# schema_v3_2.net
KiCad netlist of a schematic drawn in EAGLE
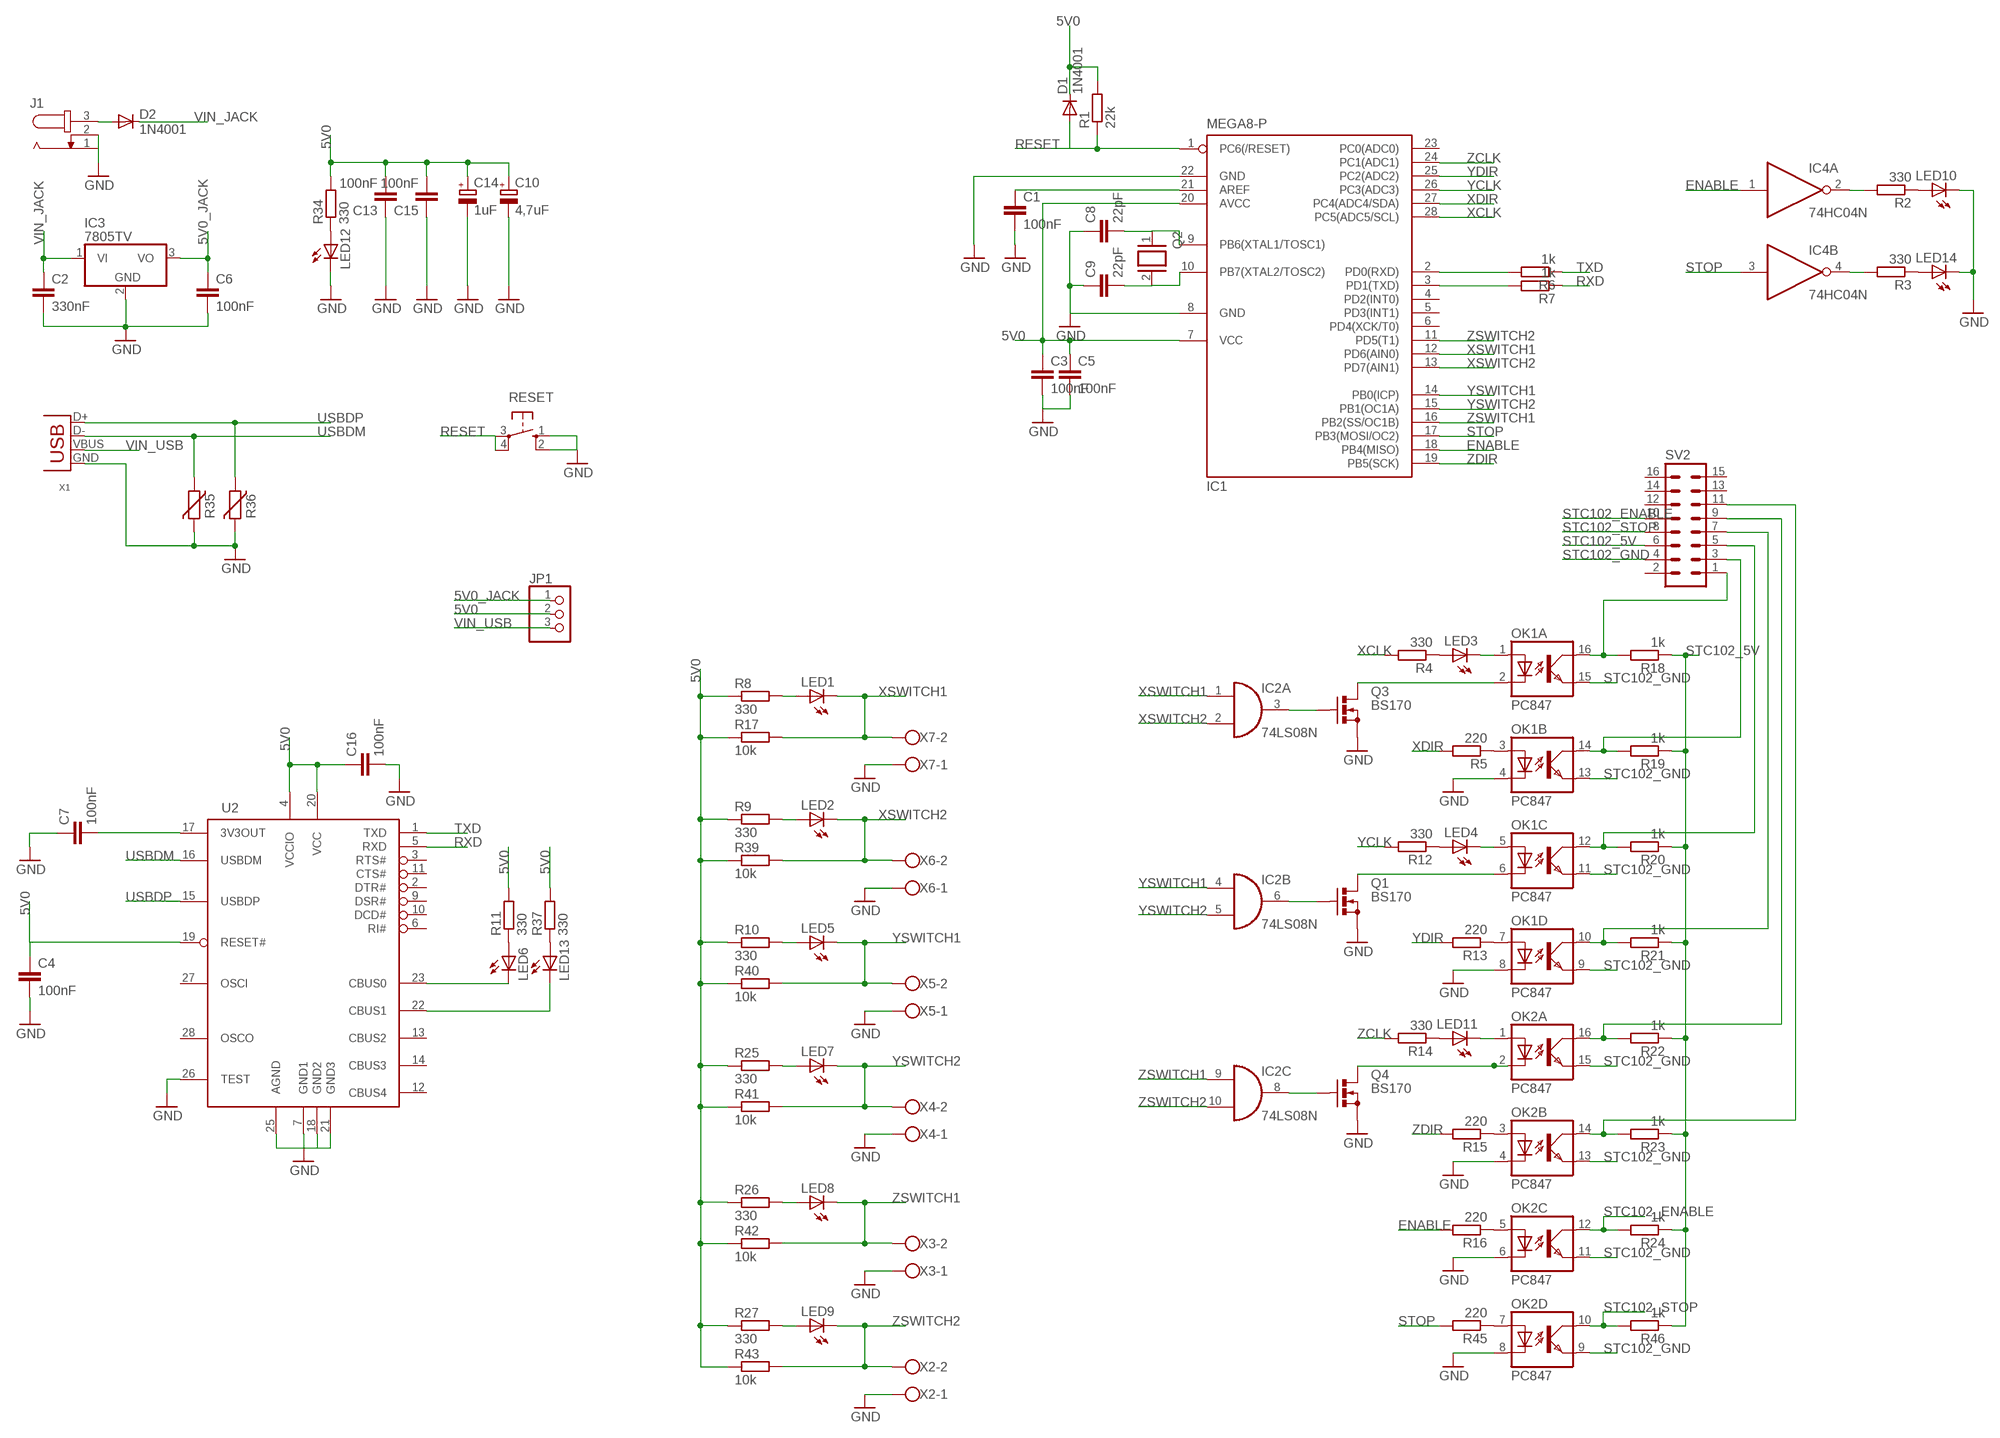
[diagram p0: schematic, sheet 1]

(export (version "E")
  (design (tool "Eeschema 10.0.6"))
  (components
    (comp (ref "C1")
      (value "100nF")
      (footprint "eagle-import:C0805")
      (libsource (lib "eagle-import") (part "C-EUC0805"))
    )
    (comp (ref "C2")
      (value "330nF")
      (footprint "eagle-import:C025-025X050")
      (libsource (lib "eagle-import") (part "C-EU025-025X050"))
    )
    (comp (ref "C3")
      (value "100nF")
      (footprint "eagle-import:C025-025X050")
      (libsource (lib "eagle-import") (part "C-EU025-025X050"))
    )
    (comp (ref "C4")
      (value "100nF")
      (footprint "eagle-import:C0603K")
      (libsource (lib "eagle-import") (part "C-EUC0603K"))
    )
    (comp (ref "C5")
      (value "100nF")
      (footprint "eagle-import:C025-025X050")
      (libsource (lib "eagle-import") (part "C-EU025-025X050"))
    )
    (comp (ref "C6")
      (value "100nF")
      (footprint "eagle-import:C025-025X050")
      (libsource (lib "eagle-import") (part "C-EU025-025X050"))
    )
    (comp (ref "C7")
      (value "100nF")
      (footprint "eagle-import:C0603K")
      (libsource (lib "eagle-import") (part "C-EUC0603K"))
    )
    (comp (ref "C8")
      (value "22pF")
      (footprint "eagle-import:C025-025X050")
      (libsource (lib "eagle-import") (part "C-EU025-025X050"))
    )
    (comp (ref "C9")
      (value "22pF")
      (footprint "eagle-import:C025-025X050")
      (libsource (lib "eagle-import") (part "C-EU025-025X050"))
    )
    (comp (ref "C10")
      (value "4,7uF")
      (footprint "eagle-import:E2,5-5")
      (libsource (lib "eagle-import") (part "CPOL-EUE2.5-5"))
    )
    (comp (ref "C13")
      (value "100nF")
      (footprint "eagle-import:C025-025X050")
      (libsource (lib "eagle-import") (part "C-EU025-025X050"))
    )
    (comp (ref "C14")
      (value "1uF")
      (footprint "eagle-import:E2,5-5")
      (libsource (lib "eagle-import") (part "CPOL-EUE2.5-5"))
    )
    (comp (ref "C15")
      (value "100nF")
      (footprint "eagle-import:C025-025X050")
      (libsource (lib "eagle-import") (part "C-EU025-025X050"))
    )
    (comp (ref "C16")
      (value "100nF")
      (footprint "eagle-import:C0603K")
      (libsource (lib "eagle-import") (part "C-EUC0603K"))
    )
    (comp (ref "D1")
      (value "1N4001")
      (footprint "eagle-import:DO41-10")
      (libsource (lib "eagle-import") (part "1N4004"))
    )
    (comp (ref "D2")
      (value "1N4001")
      (footprint "eagle-import:DO41-10")
      (libsource (lib "eagle-import") (part "1N4004"))
    )
    (comp (ref "IC1")
      (value "MEGA8-P")
      (footprint "eagle-import:DIL28-3")
      (libsource (lib "eagle-import") (part "MEGA8-P"))
    )
    (comp (ref "IC2")
      (value "74LS08N")
      (footprint "eagle-import:DIL14")
      (libsource (lib "eagle-import") (part "7408NLS"))
    )
    (comp (ref "IC3")
      (value "7805TV")
      (footprint "eagle-import:TO220V")
      (libsource (lib "eagle-import") (part "78TV05"))
    )
    (comp (ref "IC4")
      (value "74HC04N")
      (footprint "eagle-import:DIL14")
      (libsource (lib "eagle-import") (part "7404NHC"))
    )
    (comp (ref "J1")
      (value "JACK-PLUG0")
      (footprint "eagle-import:SPC4077")
      (libsource (lib "eagle-import") (part "JACK-PLUG0"))
    )
    (comp (ref "JP1")
      (value "PINHD-1X3")
      (footprint "eagle-import:1X03")
      (libsource (lib "eagle-import") (part "PINHD-1X3"))
    )
    (comp (ref "LED1")
      (value "LED3MM")
      (footprint "eagle-import:LED3MM")
      (libsource (lib "eagle-import") (part "LED3MM"))
    )
    (comp (ref "LED2")
      (value "LED3MM")
      (footprint "eagle-import:LED3MM")
      (libsource (lib "eagle-import") (part "LED3MM"))
    )
    (comp (ref "LED3")
      (value "LED3MM")
      (footprint "eagle-import:LED3MM")
      (libsource (lib "eagle-import") (part "LED3MM"))
    )
    (comp (ref "LED4")
      (value "LED3MM")
      (footprint "eagle-import:LED3MM")
      (libsource (lib "eagle-import") (part "LED3MM"))
    )
    (comp (ref "LED5")
      (value "LED3MM")
      (footprint "eagle-import:LED3MM")
      (libsource (lib "eagle-import") (part "LED3MM"))
    )
    (comp (ref "LED6")
      (value "LED3MM")
      (footprint "eagle-import:LED3MM")
      (libsource (lib "eagle-import") (part "LED3MM"))
    )
    (comp (ref "LED7")
      (value "LED3MM")
      (footprint "eagle-import:LED3MM")
      (libsource (lib "eagle-import") (part "LED3MM"))
    )
    (comp (ref "LED8")
      (value "LED3MM")
      (footprint "eagle-import:LED3MM")
      (libsource (lib "eagle-import") (part "LED3MM"))
    )
    (comp (ref "LED9")
      (value "LED3MM")
      (footprint "eagle-import:LED3MM")
      (libsource (lib "eagle-import") (part "LED3MM"))
    )
    (comp (ref "LED10")
      (value "LED3MM")
      (footprint "eagle-import:LED3MM")
      (libsource (lib "eagle-import") (part "LED3MM"))
    )
    (comp (ref "LED11")
      (value "LED3MM")
      (footprint "eagle-import:LED3MM")
      (libsource (lib "eagle-import") (part "LED3MM"))
    )
    (comp (ref "LED12")
      (value "LED3MM")
      (footprint "eagle-import:LED3MM")
      (libsource (lib "eagle-import") (part "LED3MM"))
    )
    (comp (ref "LED13")
      (value "LED3MM")
      (footprint "eagle-import:LED3MM")
      (libsource (lib "eagle-import") (part "LED3MM"))
    )
    (comp (ref "LED14")
      (value "LED3MM")
      (footprint "eagle-import:LED3MM")
      (libsource (lib "eagle-import") (part "LED3MM"))
    )
    (comp (ref "OK1")
      (value "PC847")
      (footprint "eagle-import:DIL16")
      (libsource (lib "eagle-import") (part "PC847"))
    )
    (comp (ref "OK2")
      (value "PC847")
      (footprint "eagle-import:DIL16")
      (libsource (lib "eagle-import") (part "PC847"))
    )
    (comp (ref "Q1")
      (value "BS170")
      (footprint "eagle-import:SOT54E")
      (libsource (lib "eagle-import") (part "BS170"))
    )
    (comp (ref "Q2")
      (value "XTAL/S")
      (footprint "eagle-import:QS")
      (libsource (lib "eagle-import") (part "XTAL/S"))
    )
    (comp (ref "Q3")
      (value "BS170")
      (footprint "eagle-import:SOT54E")
      (libsource (lib "eagle-import") (part "BS170"))
    )
    (comp (ref "Q4")
      (value "BS170")
      (footprint "eagle-import:SOT54E")
      (libsource (lib "eagle-import") (part "BS170"))
    )
    (comp (ref "R1")
      (value "22k")
      (footprint "eagle-import:0207_10")
      (libsource (lib "eagle-import") (part "R-EU_0207/10"))
    )
    (comp (ref "R2")
      (value "330")
      (footprint "eagle-import:0207_10")
      (libsource (lib "eagle-import") (part "R-EU_0207/10"))
    )
    (comp (ref "R3")
      (value "330")
      (footprint "eagle-import:0207_10")
      (libsource (lib "eagle-import") (part "R-EU_0207/10"))
    )
    (comp (ref "R4")
      (value "330")
      (footprint "eagle-import:0207_10")
      (libsource (lib "eagle-import") (part "R-EU_0207/10"))
    )
    (comp (ref "R5")
      (value "220")
      (footprint "eagle-import:0207_10")
      (libsource (lib "eagle-import") (part "R-EU_0207/10"))
    )
    (comp (ref "R6")
      (value "1k")
      (footprint "eagle-import:0207_10")
      (libsource (lib "eagle-import") (part "R-EU_0207/10"))
    )
    (comp (ref "R7")
      (value "1k")
      (footprint "eagle-import:0207_10")
      (libsource (lib "eagle-import") (part "R-EU_0207/10"))
    )
    (comp (ref "R8")
      (value "330")
      (footprint "eagle-import:0207_10")
      (libsource (lib "eagle-import") (part "R-EU_0207/10"))
    )
    (comp (ref "R9")
      (value "330")
      (footprint "eagle-import:0207_10")
      (libsource (lib "eagle-import") (part "R-EU_0207/10"))
    )
    (comp (ref "R10")
      (value "330")
      (footprint "eagle-import:0207_10")
      (libsource (lib "eagle-import") (part "R-EU_0207/10"))
    )
    (comp (ref "R11")
      (value "330")
      (footprint "eagle-import:0207_10")
      (libsource (lib "eagle-import") (part "R-EU_0207/10"))
    )
    (comp (ref "R12")
      (value "330")
      (footprint "eagle-import:0207_10")
      (libsource (lib "eagle-import") (part "R-EU_0207/10"))
    )
    (comp (ref "R13")
      (value "220")
      (footprint "eagle-import:0207_10")
      (libsource (lib "eagle-import") (part "R-EU_0207/10"))
    )
    (comp (ref "R14")
      (value "330")
      (footprint "eagle-import:0207_10")
      (libsource (lib "eagle-import") (part "R-EU_0207/10"))
    )
    (comp (ref "R15")
      (value "220")
      (footprint "eagle-import:0207_10")
      (libsource (lib "eagle-import") (part "R-EU_0207/10"))
    )
    (comp (ref "R16")
      (value "220")
      (footprint "eagle-import:0207_10")
      (libsource (lib "eagle-import") (part "R-EU_0207/10"))
    )
    (comp (ref "R17")
      (value "10k")
      (footprint "eagle-import:0207_10")
      (libsource (lib "eagle-import") (part "R-EU_0207/10"))
    )
    (comp (ref "R18")
      (value "1k")
      (footprint "eagle-import:0207_10")
      (libsource (lib "eagle-import") (part "R-EU_0207/10"))
    )
    (comp (ref "R19")
      (value "1k")
      (footprint "eagle-import:0207_10")
      (libsource (lib "eagle-import") (part "R-EU_0207/10"))
    )
    (comp (ref "R20")
      (value "1k")
      (footprint "eagle-import:0207_10")
      (libsource (lib "eagle-import") (part "R-EU_0207/10"))
    )
    (comp (ref "R21")
      (value "1k")
      (footprint "eagle-import:0207_10")
      (libsource (lib "eagle-import") (part "R-EU_0207/10"))
    )
    (comp (ref "R22")
      (value "1k")
      (footprint "eagle-import:0207_10")
      (libsource (lib "eagle-import") (part "R-EU_0207/10"))
    )
    (comp (ref "R23")
      (value "1k")
      (footprint "eagle-import:0207_10")
      (libsource (lib "eagle-import") (part "R-EU_0207/10"))
    )
    (comp (ref "R24")
      (value "1k")
      (footprint "eagle-import:0207_10")
      (libsource (lib "eagle-import") (part "R-EU_0207/10"))
    )
    (comp (ref "R25")
      (value "330")
      (footprint "eagle-import:0207_10")
      (libsource (lib "eagle-import") (part "R-EU_0207/10"))
    )
    (comp (ref "R26")
      (value "330")
      (footprint "eagle-import:0207_10")
      (libsource (lib "eagle-import") (part "R-EU_0207/10"))
    )
    (comp (ref "R27")
      (value "330")
      (footprint "eagle-import:0207_10")
      (libsource (lib "eagle-import") (part "R-EU_0207/10"))
    )
    (comp (ref "R34")
      (value "330")
      (footprint "eagle-import:0207_10")
      (libsource (lib "eagle-import") (part "R-EU_0207/10"))
    )
    (comp (ref "R35")
      (value "VARISTORCN0603")
      (footprint "eagle-import:CT_CN0603")
      (libsource (lib "eagle-import") (part "VARISTORCN0603"))
    )
    (comp (ref "R36")
      (value "VARISTORCN0603")
      (footprint "eagle-import:CT_CN0603")
      (libsource (lib "eagle-import") (part "VARISTORCN0603"))
    )
    (comp (ref "R37")
      (value "330")
      (footprint "eagle-import:0207_10")
      (libsource (lib "eagle-import") (part "R-EU_0207/10"))
    )
    (comp (ref "R39")
      (value "10k")
      (footprint "eagle-import:0207_10")
      (libsource (lib "eagle-import") (part "R-EU_0207/10"))
    )
    (comp (ref "R40")
      (value "10k")
      (footprint "eagle-import:0207_10")
      (libsource (lib "eagle-import") (part "R-EU_0207/10"))
    )
    (comp (ref "R41")
      (value "10k")
      (footprint "eagle-import:0207_10")
      (libsource (lib "eagle-import") (part "R-EU_0207/10"))
    )
    (comp (ref "R42")
      (value "10k")
      (footprint "eagle-import:0207_10")
      (libsource (lib "eagle-import") (part "R-EU_0207/10"))
    )
    (comp (ref "R43")
      (value "10k")
      (footprint "eagle-import:0207_10")
      (libsource (lib "eagle-import") (part "R-EU_0207/10"))
    )
    (comp (ref "R45")
      (value "220")
      (footprint "eagle-import:0207_10")
      (libsource (lib "eagle-import") (part "R-EU_0207/10"))
    )
    (comp (ref "R46")
      (value "1k")
      (footprint "eagle-import:0207_10")
      (libsource (lib "eagle-import") (part "R-EU_0207/10"))
    )
    (comp (ref "RESET")
      (value "10-XX")
      (footprint "eagle-import:B3F-10XX")
      (fields (field (name "MPN") "B3F-1000"))
      (libsource (lib "eagle-import") (part "10-XX"))
    )
    (comp (ref "SV2")
      (value "MA08-2")
      (footprint "eagle-import:MA08-2")
      (libsource (lib "eagle-import") (part "MA08-2"))
    )
    (comp (ref "U2")
      (value "FT232RL")
      (footprint "eagle-import:SSOP28DB")
      (libsource (lib "eagle-import") (part "FT232RL"))
    )
    (comp (ref "X1")
      (value "USB-B-H")
      (footprint "eagle-import:USB-B-H")
      (libsource (lib "eagle-import") (part "USB-B-H"))
    )
    (comp (ref "X2")
      (value "W237-102")
      (footprint "eagle-import:W237-102")
      (fields (field (name "MPN") "237-102"))
      (libsource (lib "eagle-import") (part "W237-102"))
    )
    (comp (ref "X3")
      (value "W237-102")
      (footprint "eagle-import:W237-102")
      (fields (field (name "MPN") "237-102"))
      (libsource (lib "eagle-import") (part "W237-102"))
    )
    (comp (ref "X4")
      (value "W237-102")
      (footprint "eagle-import:W237-102")
      (fields (field (name "MPN") "237-102"))
      (libsource (lib "eagle-import") (part "W237-102"))
    )
    (comp (ref "X5")
      (value "W237-102")
      (footprint "eagle-import:W237-102")
      (fields (field (name "MPN") "237-102"))
      (libsource (lib "eagle-import") (part "W237-102"))
    )
    (comp (ref "X6")
      (value "W237-102")
      (footprint "eagle-import:W237-102")
      (fields (field (name "MPN") "237-102"))
      (libsource (lib "eagle-import") (part "W237-102"))
    )
    (comp (ref "X7")
      (value "W237-102")
      (footprint "eagle-import:W237-102")
      (fields (field (name "MPN") "237-102"))
      (libsource (lib "eagle-import") (part "W237-102"))
    )
  )
  (nets
    (net (code "1") (name "/5V0") (class "Default")
      (node (ref "C10") (pin "+") (pinfunction "+_+") (pintype "passive"))
      (node (ref "C13") (pin "2") (pinfunction "2_2") (pintype "passive"))
      (node (ref "C14") (pin "+") (pinfunction "+_+") (pintype "passive"))
      (node (ref "C15") (pin "2") (pinfunction "2_2") (pintype "passive"))
      (node (ref "C16") (pin "1") (pinfunction "1_1") (pintype "passive"))
      (node (ref "C3") (pin "1") (pinfunction "1_1") (pintype "passive"))
      (node (ref "C4") (pin "1") (pinfunction "1_1") (pintype "passive"))
      (node (ref "C5") (pin "1") (pinfunction "1_1") (pintype "passive"))
      (node (ref "D1") (pin "C") (pinfunction "C_C") (pintype "passive"))
      (node (ref "IC1") (pin "20") (pinfunction "AVCC_20") (pintype "power_in"))
      (node (ref "IC1") (pin "7") (pinfunction "VCC_7") (pintype "power_in"))
      (node (ref "JP1") (pin "2") (pinfunction "2_2") (pintype "passive"))
      (node (ref "R1") (pin "2") (pinfunction "2_2") (pintype "passive"))
      (node (ref "R10") (pin "1") (pinfunction "1_1") (pintype "passive"))
      (node (ref "R11") (pin "2") (pinfunction "2_2") (pintype "passive"))
      (node (ref "R17") (pin "1") (pinfunction "1_1") (pintype "passive"))
      (node (ref "R25") (pin "1") (pinfunction "1_1") (pintype "passive"))
      (node (ref "R26") (pin "1") (pinfunction "1_1") (pintype "passive"))
      (node (ref "R27") (pin "1") (pinfunction "1_1") (pintype "passive"))
      (node (ref "R34") (pin "2") (pinfunction "2_2") (pintype "passive"))
      (node (ref "R37") (pin "2") (pinfunction "2_2") (pintype "passive"))
      (node (ref "R39") (pin "1") (pinfunction "1_1") (pintype "passive"))
      (node (ref "R40") (pin "1") (pinfunction "1_1") (pintype "passive"))
      (node (ref "R41") (pin "1") (pinfunction "1_1") (pintype "passive"))
      (node (ref "R42") (pin "1") (pinfunction "1_1") (pintype "passive"))
      (node (ref "R43") (pin "1") (pinfunction "1_1") (pintype "passive"))
      (node (ref "R8") (pin "1") (pinfunction "1_1") (pintype "passive"))
      (node (ref "R9") (pin "1") (pinfunction "1_1") (pintype "passive"))
      (node (ref "U2") (pin "19") (pinfunction "RESET#_19") (pintype "input"))
      (node (ref "U2") (pin "20") (pinfunction "VCC_20") (pintype "power_in"))
      (node (ref "U2") (pin "4") (pinfunction "VCCIO_4") (pintype "power_in"))
    )
    (net (code "2") (name "/5V0_JACK") (class "Default")
      (node (ref "C6") (pin "1") (pinfunction "1_1") (pintype "passive"))
      (node (ref "IC3") (pin "3") (pinfunction "VO_3") (pintype "passive"))
      (node (ref "JP1") (pin "1") (pinfunction "1_1") (pintype "passive"))
    )
    (net (code "3") (name "/ENABLE") (class "Default")
      (node (ref "IC1") (pin "18") (pinfunction "PB4(MISO)_18") (pintype "bidirectional"))
      (node (ref "IC4") (pin "1") (pinfunction "I_1") (pintype "input"))
      (node (ref "R16") (pin "2") (pinfunction "2_2") (pintype "passive"))
    )
    (net (code "4") (name "/RESET") (class "Default")
      (node (ref "D1") (pin "A") (pinfunction "A_A") (pintype "passive"))
      (node (ref "IC1") (pin "1") (pinfunction "PC6(/RESET)_1") (pintype "bidirectional"))
      (node (ref "R1") (pin "1") (pinfunction "1_1") (pintype "passive"))
      (node (ref "RESET") (pin "3") (pinfunction "P_3") (pintype "passive"))
      (node (ref "RESET") (pin "4") (pinfunction "P1_4") (pintype "passive"))
    )
    (net (code "5") (name "/RXD") (class "Default")
      (node (ref "R7") (pin "1") (pinfunction "1_1") (pintype "passive"))
      (node (ref "U2") (pin "5") (pinfunction "RXD_5") (pintype "input"))
    )
    (net (code "6") (name "/STC102_5V") (class "Default")
      (node (ref "R18") (pin "1") (pinfunction "1_1") (pintype "passive"))
      (node (ref "R19") (pin "1") (pinfunction "1_1") (pintype "passive"))
      (node (ref "R20") (pin "1") (pinfunction "1_1") (pintype "passive"))
      (node (ref "R21") (pin "1") (pinfunction "1_1") (pintype "passive"))
      (node (ref "R22") (pin "1") (pinfunction "1_1") (pintype "passive"))
      (node (ref "R23") (pin "1") (pinfunction "1_1") (pintype "passive"))
      (node (ref "R24") (pin "1") (pinfunction "1_1") (pintype "passive"))
      (node (ref "R46") (pin "1") (pinfunction "1_1") (pintype "passive"))
      (node (ref "SV2") (pin "6") (pinfunction "6_6") (pintype "passive"))
    )
    (net (code "7") (name "/STC102_ENABLE") (class "Default")
      (node (ref "OK2") (pin "12") (pinfunction "COL_12") (pintype "passive"))
      (node (ref "R24") (pin "2") (pinfunction "2_2") (pintype "passive"))
      (node (ref "SV2") (pin "10") (pinfunction "10_10") (pintype "passive"))
    )
    (net (code "8") (name "/STC102_GND") (class "Default")
      (node (ref "OK1") (pin "11") (pinfunction "EMIT_11") (pintype "passive"))
      (node (ref "OK1") (pin "13") (pinfunction "EMIT_13") (pintype "passive"))
      (node (ref "OK1") (pin "15") (pinfunction "EMIT_15") (pintype "passive"))
      (node (ref "OK1") (pin "9") (pinfunction "EMIT_9") (pintype "passive"))
      (node (ref "OK2") (pin "11") (pinfunction "EMIT_11") (pintype "passive"))
      (node (ref "OK2") (pin "13") (pinfunction "EMIT_13") (pintype "passive"))
      (node (ref "OK2") (pin "15") (pinfunction "EMIT_15") (pintype "passive"))
      (node (ref "OK2") (pin "9") (pinfunction "EMIT_9") (pintype "passive"))
      (node (ref "SV2") (pin "4") (pinfunction "4_4") (pintype "passive"))
    )
    (net (code "9") (name "/STC102_STOP") (class "Default")
      (node (ref "OK2") (pin "10") (pinfunction "COL_10") (pintype "passive"))
      (node (ref "R46") (pin "2") (pinfunction "2_2") (pintype "passive"))
      (node (ref "SV2") (pin "8") (pinfunction "8_8") (pintype "passive"))
    )
    (net (code "10") (name "/STOP") (class "Default")
      (node (ref "IC1") (pin "17") (pinfunction "PB3(MOSI/OC2)_17") (pintype "bidirectional"))
      (node (ref "IC4") (pin "3") (pinfunction "I_3") (pintype "input"))
      (node (ref "R45") (pin "2") (pinfunction "2_2") (pintype "passive"))
    )
    (net (code "11") (name "/TXD") (class "Default")
      (node (ref "R6") (pin "1") (pinfunction "1_1") (pintype "passive"))
      (node (ref "U2") (pin "1") (pinfunction "TXD_1") (pintype "output"))
    )
    (net (code "12") (name "/USBDM") (class "Default")
      (node (ref "R35") (pin "1") (pinfunction "1_1") (pintype "passive"))
      (node (ref "U2") (pin "16") (pinfunction "USBDM_16") (pintype "bidirectional"))
      (node (ref "X1") (pin "D-") (pinfunction "D-_D-") (pintype "bidirectional"))
    )
    (net (code "13") (name "/USBDP") (class "Default")
      (node (ref "R36") (pin "1") (pinfunction "1_1") (pintype "passive"))
      (node (ref "U2") (pin "15") (pinfunction "USBDP_15") (pintype "bidirectional"))
      (node (ref "X1") (pin "D+") (pinfunction "D+_D+") (pintype "bidirectional"))
    )
    (net (code "14") (name "/VIN_JACK") (class "Default")
      (node (ref "C2") (pin "1") (pinfunction "1_1") (pintype "passive"))
      (node (ref "D2") (pin "C") (pinfunction "C_C") (pintype "passive"))
      (node (ref "IC3") (pin "1") (pinfunction "VI_1") (pintype "input"))
    )
    (net (code "15") (name "/VIN_USB") (class "Default")
      (node (ref "JP1") (pin "3") (pinfunction "3_3") (pintype "passive"))
      (node (ref "X1") (pin "VBUS") (pinfunction "VBUS_VBUS") (pintype "bidirectional"))
    )
    (net (code "16") (name "/XCLK") (class "Default")
      (node (ref "IC1") (pin "28") (pinfunction "PC5(ADC5/SCL)_28") (pintype "bidirectional"))
      (node (ref "R4") (pin "2") (pinfunction "2_2") (pintype "passive"))
    )
    (net (code "17") (name "/XDIR") (class "Default")
      (node (ref "IC1") (pin "27") (pinfunction "PC4(ADC4/SDA)_27") (pintype "bidirectional"))
      (node (ref "R5") (pin "2") (pinfunction "2_2") (pintype "passive"))
    )
    (net (code "18") (name "/XSWITCH1") (class "Default")
      (node (ref "IC1") (pin "12") (pinfunction "PD6(AIN0)_12") (pintype "bidirectional"))
      (node (ref "IC2") (pin "1") (pinfunction "I0_1") (pintype "input"))
      (node (ref "LED1") (pin "K") (pinfunction "C_K") (pintype "passive"))
      (node (ref "R17") (pin "2") (pinfunction "2_2") (pintype "passive"))
      (node (ref "X7") (pin "2") (pinfunction "KL_2") (pintype "passive"))
    )
    (net (code "19") (name "/XSWITCH2") (class "Default")
      (node (ref "IC1") (pin "13") (pinfunction "PD7(AIN1)_13") (pintype "bidirectional"))
      (node (ref "IC2") (pin "2") (pinfunction "I1_2") (pintype "input"))
      (node (ref "LED2") (pin "K") (pinfunction "C_K") (pintype "passive"))
      (node (ref "R39") (pin "2") (pinfunction "2_2") (pintype "passive"))
      (node (ref "X6") (pin "2") (pinfunction "KL_2") (pintype "passive"))
    )
    (net (code "20") (name "/YCLK") (class "Default")
      (node (ref "IC1") (pin "26") (pinfunction "PC3(ADC3)_26") (pintype "bidirectional"))
      (node (ref "R12") (pin "2") (pinfunction "2_2") (pintype "passive"))
    )
    (net (code "21") (name "/YDIR") (class "Default")
      (node (ref "IC1") (pin "25") (pinfunction "PC2(ADC2)_25") (pintype "bidirectional"))
      (node (ref "R13") (pin "2") (pinfunction "2_2") (pintype "passive"))
    )
    (net (code "22") (name "/YSWITCH1") (class "Default")
      (node (ref "IC1") (pin "14") (pinfunction "PB0(ICP)_14") (pintype "bidirectional"))
      (node (ref "IC2") (pin "4") (pinfunction "I0_4") (pintype "input"))
      (node (ref "LED5") (pin "K") (pinfunction "C_K") (pintype "passive"))
      (node (ref "R40") (pin "2") (pinfunction "2_2") (pintype "passive"))
      (node (ref "X5") (pin "2") (pinfunction "KL_2") (pintype "passive"))
    )
    (net (code "23") (name "/YSWITCH2") (class "Default")
      (node (ref "IC1") (pin "15") (pinfunction "PB1(OC1A)_15") (pintype "bidirectional"))
      (node (ref "IC2") (pin "5") (pinfunction "I1_5") (pintype "input"))
      (node (ref "LED7") (pin "K") (pinfunction "C_K") (pintype "passive"))
      (node (ref "R41") (pin "2") (pinfunction "2_2") (pintype "passive"))
      (node (ref "X4") (pin "2") (pinfunction "KL_2") (pintype "passive"))
    )
    (net (code "24") (name "/ZCLK") (class "Default")
      (node (ref "IC1") (pin "24") (pinfunction "PC1(ADC1)_24") (pintype "bidirectional"))
      (node (ref "R14") (pin "2") (pinfunction "2_2") (pintype "passive"))
    )
    (net (code "25") (name "/ZDIR") (class "Default")
      (node (ref "IC1") (pin "19") (pinfunction "PB5(SCK)_19") (pintype "bidirectional"))
      (node (ref "R15") (pin "2") (pinfunction "2_2") (pintype "passive"))
    )
    (net (code "26") (name "/ZSWITCH1") (class "Default")
      (node (ref "IC1") (pin "16") (pinfunction "PB2(SS/OC1B)_16") (pintype "bidirectional"))
      (node (ref "IC2") (pin "9") (pinfunction "I0_9") (pintype "input"))
      (node (ref "LED8") (pin "K") (pinfunction "C_K") (pintype "passive"))
      (node (ref "R42") (pin "2") (pinfunction "2_2") (pintype "passive"))
      (node (ref "X3") (pin "2") (pinfunction "KL_2") (pintype "passive"))
    )
    (net (code "27") (name "/ZSWITCH2") (class "Default")
      (node (ref "IC1") (pin "11") (pinfunction "PD5(T1)_11") (pintype "bidirectional"))
      (node (ref "IC2") (pin "10") (pinfunction "I1_10") (pintype "input"))
      (node (ref "LED9") (pin "K") (pinfunction "C_K") (pintype "passive"))
      (node (ref "R43") (pin "2") (pinfunction "2_2") (pintype "passive"))
      (node (ref "X2") (pin "2") (pinfunction "KL_2") (pintype "passive"))
    )
    (net (code "28") (name "GND") (class "Default")
      (node (ref "C1") (pin "2") (pinfunction "2_2") (pintype "passive"))
      (node (ref "C10") (pin "-") (pinfunction "-_-") (pintype "passive"))
      (node (ref "C13") (pin "1") (pinfunction "1_1") (pintype "passive"))
      (node (ref "C14") (pin "-") (pinfunction "-_-") (pintype "passive"))
      (node (ref "C15") (pin "1") (pinfunction "1_1") (pintype "passive"))
      (node (ref "C16") (pin "2") (pinfunction "2_2") (pintype "passive"))
      (node (ref "C2") (pin "2") (pinfunction "2_2") (pintype "passive"))
      (node (ref "C3") (pin "2") (pinfunction "2_2") (pintype "passive"))
      (node (ref "C4") (pin "2") (pinfunction "2_2") (pintype "passive"))
      (node (ref "C5") (pin "2") (pinfunction "2_2") (pintype "passive"))
      (node (ref "C6") (pin "2") (pinfunction "2_2") (pintype "passive"))
      (node (ref "C7") (pin "1") (pinfunction "1_1") (pintype "passive"))
      (node (ref "C8") (pin "1") (pinfunction "1_1") (pintype "passive"))
      (node (ref "C9") (pin "1") (pinfunction "1_1") (pintype "passive"))
      (node (ref "IC1") (pin "22") (pinfunction "GND_22") (pintype "power_in"))
      (node (ref "IC1") (pin "8") (pinfunction "GND_8") (pintype "power_in"))
      (node (ref "IC3") (pin "2") (pinfunction "GND_2") (pintype "passive"))
      (node (ref "J1") (pin "1") (pinfunction "1_1") (pintype "passive"))
      (node (ref "J1") (pin "2") (pinfunction "2_2") (pintype "passive"))
      (node (ref "LED10") (pin "K") (pinfunction "C_K") (pintype "passive"))
      (node (ref "LED12") (pin "K") (pinfunction "C_K") (pintype "passive"))
      (node (ref "LED14") (pin "K") (pinfunction "C_K") (pintype "passive"))
      (node (ref "OK1") (pin "4") (pinfunction "C_4") (pintype "passive"))
      (node (ref "OK1") (pin "8") (pinfunction "C_8") (pintype "passive"))
      (node (ref "OK2") (pin "4") (pinfunction "C_4") (pintype "passive"))
      (node (ref "OK2") (pin "6") (pinfunction "C_6") (pintype "passive"))
      (node (ref "OK2") (pin "8") (pinfunction "C_8") (pintype "passive"))
      (node (ref "Q1") (pin "S") (pinfunction "S_S") (pintype "passive"))
      (node (ref "Q3") (pin "S") (pinfunction "S_S") (pintype "passive"))
      (node (ref "Q4") (pin "S") (pinfunction "S_S") (pintype "passive"))
      (node (ref "R35") (pin "2") (pinfunction "2_2") (pintype "passive"))
      (node (ref "R36") (pin "2") (pinfunction "2_2") (pintype "passive"))
      (node (ref "RESET") (pin "1") (pinfunction "S_1") (pintype "passive"))
      (node (ref "RESET") (pin "2") (pinfunction "S1_2") (pintype "passive"))
      (node (ref "U2") (pin "18") (pinfunction "GND2_18") (pintype "power_in"))
      (node (ref "U2") (pin "21") (pinfunction "GND3_21") (pintype "power_in"))
      (node (ref "U2") (pin "25") (pinfunction "AGND_25") (pintype "power_in"))
      (node (ref "U2") (pin "26") (pinfunction "TEST_26") (pintype "input"))
      (node (ref "U2") (pin "7") (pinfunction "GND1_7") (pintype "power_in"))
      (node (ref "X1") (pin "GND") (pinfunction "GND_GND") (pintype "bidirectional"))
      (node (ref "X2") (pin "1") (pinfunction "KL_1") (pintype "passive"))
      (node (ref "X3") (pin "1") (pinfunction "KL_1") (pintype "passive"))
      (node (ref "X4") (pin "1") (pinfunction "KL_1") (pintype "passive"))
      (node (ref "X5") (pin "1") (pinfunction "KL_1") (pintype "passive"))
      (node (ref "X6") (pin "1") (pinfunction "KL_1") (pintype "passive"))
      (node (ref "X7") (pin "1") (pinfunction "KL_1") (pintype "passive"))
    )
    (net (code "29") (name "Net-(D2-PadA)") (class "Default")
      (node (ref "D2") (pin "A") (pinfunction "A_A") (pintype "passive"))
      (node (ref "J1") (pin "3") (pinfunction "3_3") (pintype "passive"))
    )
    (net (code "30") (name "Net-(IC1-AREF)") (class "Default")
      (node (ref "C1") (pin "1") (pinfunction "1_1") (pintype "passive"))
      (node (ref "IC1") (pin "21") (pinfunction "AREF_21") (pintype "passive"))
    )
    (net (code "31") (name "Net-(IC1-PB6(XTAL1{slash}TOSC1))") (class "Default")
      (node (ref "C8") (pin "2") (pinfunction "2_2") (pintype "passive"))
      (node (ref "IC1") (pin "9") (pinfunction "PB6(XTAL1/TOSC1)_9") (pintype "bidirectional"))
      (node (ref "Q2") (pin "1") (pinfunction "1_1") (pintype "passive"))
    )
    (net (code "32") (name "Net-(IC1-PB7(XTAL2{slash}TOSC2))") (class "Default")
      (node (ref "C9") (pin "2") (pinfunction "2_2") (pintype "passive"))
      (node (ref "IC1") (pin "10") (pinfunction "PB7(XTAL2/TOSC2)_10") (pintype "bidirectional"))
      (node (ref "Q2") (pin "2") (pinfunction "2_2") (pintype "passive"))
    )
    (net (code "33") (name "Net-(IC1-PD0(RXD))") (class "Default")
      (node (ref "IC1") (pin "2") (pinfunction "PD0(RXD)_2") (pintype "bidirectional"))
      (node (ref "R6") (pin "2") (pinfunction "2_2") (pintype "passive"))
    )
    (net (code "34") (name "Net-(IC1-PD1(TXD))") (class "Default")
      (node (ref "IC1") (pin "3") (pinfunction "PD1(TXD)_3") (pintype "bidirectional"))
      (node (ref "R7") (pin "2") (pinfunction "2_2") (pintype "passive"))
    )
    (net (code "35") (name "Net-(IC2A-O)") (class "Default")
      (node (ref "IC2") (pin "3") (pinfunction "O_3") (pintype "output"))
      (node (ref "Q3") (pin "G") (pinfunction "G_G") (pintype "passive"))
    )
    (net (code "36") (name "Net-(IC2B-O)") (class "Default")
      (node (ref "IC2") (pin "6") (pinfunction "O_6") (pintype "output"))
      (node (ref "Q1") (pin "G") (pinfunction "G_G") (pintype "passive"))
    )
    (net (code "37") (name "Net-(IC2C-O)") (class "Default")
      (node (ref "IC2") (pin "8") (pinfunction "O_8") (pintype "output"))
      (node (ref "Q4") (pin "G") (pinfunction "G_G") (pintype "passive"))
    )
    (net (code "38") (name "Net-(IC4A-O)") (class "Default")
      (node (ref "IC4") (pin "2") (pinfunction "O_2") (pintype "output"))
      (node (ref "R2") (pin "2") (pinfunction "2_2") (pintype "passive"))
    )
    (net (code "39") (name "Net-(IC4B-O)") (class "Default")
      (node (ref "IC4") (pin "4") (pinfunction "O_4") (pintype "output"))
      (node (ref "R3") (pin "2") (pinfunction "2_2") (pintype "passive"))
    )
    (net (code "40") (name "Net-(LED1-PadA)") (class "Default")
      (node (ref "LED1") (pin "A") (pinfunction "A_A") (pintype "passive"))
      (node (ref "R8") (pin "2") (pinfunction "2_2") (pintype "passive"))
    )
    (net (code "41") (name "Net-(LED2-PadA)") (class "Default")
      (node (ref "LED2") (pin "A") (pinfunction "A_A") (pintype "passive"))
      (node (ref "R9") (pin "2") (pinfunction "2_2") (pintype "passive"))
    )
    (net (code "42") (name "Net-(LED3-C)") (class "Default")
      (node (ref "LED3") (pin "K") (pinfunction "C_K") (pintype "passive"))
      (node (ref "OK1") (pin "1") (pinfunction "A_1") (pintype "passive"))
    )
    (net (code "43") (name "Net-(LED3-PadA)") (class "Default")
      (node (ref "LED3") (pin "A") (pinfunction "A_A") (pintype "passive"))
      (node (ref "R4") (pin "1") (pinfunction "1_1") (pintype "passive"))
    )
    (net (code "44") (name "Net-(LED4-C)") (class "Default")
      (node (ref "LED4") (pin "K") (pinfunction "C_K") (pintype "passive"))
      (node (ref "OK1") (pin "5") (pinfunction "A_5") (pintype "passive"))
    )
    (net (code "45") (name "Net-(LED4-PadA)") (class "Default")
      (node (ref "LED4") (pin "A") (pinfunction "A_A") (pintype "passive"))
      (node (ref "R12") (pin "1") (pinfunction "1_1") (pintype "passive"))
    )
    (net (code "46") (name "Net-(LED5-PadA)") (class "Default")
      (node (ref "LED5") (pin "A") (pinfunction "A_A") (pintype "passive"))
      (node (ref "R10") (pin "2") (pinfunction "2_2") (pintype "passive"))
    )
    (net (code "47") (name "Net-(LED6-C)") (class "Default")
      (node (ref "LED6") (pin "K") (pinfunction "C_K") (pintype "passive"))
      (node (ref "U2") (pin "23") (pinfunction "CBUS0_23") (pintype "bidirectional"))
    )
    (net (code "48") (name "Net-(LED6-PadA)") (class "Default")
      (node (ref "LED6") (pin "A") (pinfunction "A_A") (pintype "passive"))
      (node (ref "R11") (pin "1") (pinfunction "1_1") (pintype "passive"))
    )
    (net (code "49") (name "Net-(LED7-PadA)") (class "Default")
      (node (ref "LED7") (pin "A") (pinfunction "A_A") (pintype "passive"))
      (node (ref "R25") (pin "2") (pinfunction "2_2") (pintype "passive"))
    )
    (net (code "50") (name "Net-(LED8-PadA)") (class "Default")
      (node (ref "LED8") (pin "A") (pinfunction "A_A") (pintype "passive"))
      (node (ref "R26") (pin "2") (pinfunction "2_2") (pintype "passive"))
    )
    (net (code "51") (name "Net-(LED9-PadA)") (class "Default")
      (node (ref "LED9") (pin "A") (pinfunction "A_A") (pintype "passive"))
      (node (ref "R27") (pin "2") (pinfunction "2_2") (pintype "passive"))
    )
    (net (code "52") (name "Net-(LED10-PadA)") (class "Default")
      (node (ref "LED10") (pin "A") (pinfunction "A_A") (pintype "passive"))
      (node (ref "R2") (pin "1") (pinfunction "1_1") (pintype "passive"))
    )
    (net (code "53") (name "Net-(LED11-C)") (class "Default")
      (node (ref "LED11") (pin "K") (pinfunction "C_K") (pintype "passive"))
      (node (ref "OK2") (pin "1") (pinfunction "A_1") (pintype "passive"))
    )
    (net (code "54") (name "Net-(LED11-PadA)") (class "Default")
      (node (ref "LED11") (pin "A") (pinfunction "A_A") (pintype "passive"))
      (node (ref "R14") (pin "1") (pinfunction "1_1") (pintype "passive"))
    )
    (net (code "55") (name "Net-(LED12-PadA)") (class "Default")
      (node (ref "LED12") (pin "A") (pinfunction "A_A") (pintype "passive"))
      (node (ref "R34") (pin "1") (pinfunction "1_1") (pintype "passive"))
    )
    (net (code "56") (name "Net-(LED13-C)") (class "Default")
      (node (ref "LED13") (pin "K") (pinfunction "C_K") (pintype "passive"))
      (node (ref "U2") (pin "22") (pinfunction "CBUS1_22") (pintype "bidirectional"))
    )
    (net (code "57") (name "Net-(LED13-PadA)") (class "Default")
      (node (ref "LED13") (pin "A") (pinfunction "A_A") (pintype "passive"))
      (node (ref "R37") (pin "1") (pinfunction "1_1") (pintype "passive"))
    )
    (net (code "58") (name "Net-(LED14-PadA)") (class "Default")
      (node (ref "LED14") (pin "A") (pinfunction "A_A") (pintype "passive"))
      (node (ref "R3") (pin "1") (pinfunction "1_1") (pintype "passive"))
    )
    (net (code "59") (name "Net-(OK1A-C)") (class "Default")
      (node (ref "OK1") (pin "2") (pinfunction "C_2") (pintype "passive"))
      (node (ref "Q3") (pin "D") (pinfunction "D_D") (pintype "passive"))
    )
    (net (code "60") (name "Net-(OK1A-COL)") (class "Default")
      (node (ref "OK1") (pin "16") (pinfunction "COL_16") (pintype "passive"))
      (node (ref "R18") (pin "2") (pinfunction "2_2") (pintype "passive"))
      (node (ref "SV2") (pin "1") (pinfunction "1_1") (pintype "passive"))
    )
    (net (code "61") (name "Net-(OK1B-A)") (class "Default")
      (node (ref "OK1") (pin "3") (pinfunction "A_3") (pintype "passive"))
      (node (ref "R5") (pin "1") (pinfunction "1_1") (pintype "passive"))
    )
    (net (code "62") (name "Net-(OK1B-COL)") (class "Default")
      (node (ref "OK1") (pin "14") (pinfunction "COL_14") (pintype "passive"))
      (node (ref "R19") (pin "2") (pinfunction "2_2") (pintype "passive"))
      (node (ref "SV2") (pin "3") (pinfunction "3_3") (pintype "passive"))
    )
    (net (code "63") (name "Net-(OK1C-C)") (class "Default")
      (node (ref "OK1") (pin "6") (pinfunction "C_6") (pintype "passive"))
      (node (ref "Q1") (pin "D") (pinfunction "D_D") (pintype "passive"))
    )
    (net (code "64") (name "Net-(OK1C-COL)") (class "Default")
      (node (ref "OK1") (pin "12") (pinfunction "COL_12") (pintype "passive"))
      (node (ref "R20") (pin "2") (pinfunction "2_2") (pintype "passive"))
      (node (ref "SV2") (pin "5") (pinfunction "5_5") (pintype "passive"))
    )
    (net (code "65") (name "Net-(OK1D-A)") (class "Default")
      (node (ref "OK1") (pin "7") (pinfunction "A_7") (pintype "passive"))
      (node (ref "R13") (pin "1") (pinfunction "1_1") (pintype "passive"))
    )
    (net (code "66") (name "Net-(OK1D-COL)") (class "Default")
      (node (ref "OK1") (pin "10") (pinfunction "COL_10") (pintype "passive"))
      (node (ref "R21") (pin "2") (pinfunction "2_2") (pintype "passive"))
      (node (ref "SV2") (pin "7") (pinfunction "7_7") (pintype "passive"))
    )
    (net (code "67") (name "Net-(OK2A-C)") (class "Default")
      (node (ref "OK2") (pin "2") (pinfunction "C_2") (pintype "passive"))
      (node (ref "Q4") (pin "D") (pinfunction "D_D") (pintype "passive"))
    )
    (net (code "68") (name "Net-(OK2A-COL)") (class "Default")
      (node (ref "OK2") (pin "16") (pinfunction "COL_16") (pintype "passive"))
      (node (ref "R22") (pin "2") (pinfunction "2_2") (pintype "passive"))
      (node (ref "SV2") (pin "9") (pinfunction "9_9") (pintype "passive"))
    )
    (net (code "69") (name "Net-(OK2B-A)") (class "Default")
      (node (ref "OK2") (pin "3") (pinfunction "A_3") (pintype "passive"))
      (node (ref "R15") (pin "1") (pinfunction "1_1") (pintype "passive"))
    )
    (net (code "70") (name "Net-(OK2B-COL)") (class "Default")
      (node (ref "OK2") (pin "14") (pinfunction "COL_14") (pintype "passive"))
      (node (ref "R23") (pin "2") (pinfunction "2_2") (pintype "passive"))
      (node (ref "SV2") (pin "11") (pinfunction "11_11") (pintype "passive"))
    )
    (net (code "71") (name "Net-(OK2C-A)") (class "Default")
      (node (ref "OK2") (pin "5") (pinfunction "A_5") (pintype "passive"))
      (node (ref "R16") (pin "1") (pinfunction "1_1") (pintype "passive"))
    )
    (net (code "72") (name "Net-(OK2D-A)") (class "Default")
      (node (ref "OK2") (pin "7") (pinfunction "A_7") (pintype "passive"))
      (node (ref "R45") (pin "1") (pinfunction "1_1") (pintype "passive"))
    )
    (net (code "73") (name "Net-(U2-3V3OUT)") (class "Default")
      (node (ref "C7") (pin "2") (pinfunction "2_2") (pintype "passive"))
      (node (ref "U2") (pin "17") (pinfunction "3V3OUT_17") (pintype "output"))
    )
    (net (code "74") (name "unconnected-(IC1-PC0(ADC0)-Pad23)") (class "Default")
      (node (ref "IC1") (pin "23") (pinfunction "PC0(ADC0)_23") (pintype "bidirectional"))
    )
    (net (code "75") (name "unconnected-(IC1-PD2(INT0)-Pad4)") (class "Default")
      (node (ref "IC1") (pin "4") (pinfunction "PD2(INT0)_4") (pintype "bidirectional"))
    )
    (net (code "76") (name "unconnected-(IC1-PD3(INT1)-Pad5)") (class "Default")
      (node (ref "IC1") (pin "5") (pinfunction "PD3(INT1)_5") (pintype "bidirectional"))
    )
    (net (code "77") (name "unconnected-(IC1-PD4(XCK{slash}T0)-Pad6)") (class "Default")
      (node (ref "IC1") (pin "6") (pinfunction "PD4(XCK/T0)_6") (pintype "bidirectional"))
    )
    (net (code "78") (name "unconnected-(SV2-Pad2)") (class "Default")
      (node (ref "SV2") (pin "2") (pinfunction "2_2") (pintype "passive"))
    )
    (net (code "79") (name "unconnected-(SV2-Pad12)") (class "Default")
      (node (ref "SV2") (pin "12") (pinfunction "12_12") (pintype "passive"))
    )
    (net (code "80") (name "unconnected-(SV2-Pad13)") (class "Default")
      (node (ref "SV2") (pin "13") (pinfunction "13_13") (pintype "passive"))
    )
    (net (code "81") (name "unconnected-(SV2-Pad14)") (class "Default")
      (node (ref "SV2") (pin "14") (pinfunction "14_14") (pintype "passive"))
    )
    (net (code "82") (name "unconnected-(SV2-Pad15)") (class "Default")
      (node (ref "SV2") (pin "15") (pinfunction "15_15") (pintype "passive"))
    )
    (net (code "83") (name "unconnected-(SV2-Pad16)") (class "Default")
      (node (ref "SV2") (pin "16") (pinfunction "16_16") (pintype "passive"))
    )
    (net (code "84") (name "unconnected-(U2-CBUS2-Pad13)") (class "Default")
      (node (ref "U2") (pin "13") (pinfunction "CBUS2_13") (pintype "bidirectional"))
    )
    (net (code "85") (name "unconnected-(U2-CBUS3-Pad14)") (class "Default")
      (node (ref "U2") (pin "14") (pinfunction "CBUS3_14") (pintype "bidirectional"))
    )
    (net (code "86") (name "unconnected-(U2-CBUS4-Pad12)") (class "Default")
      (node (ref "U2") (pin "12") (pinfunction "CBUS4_12") (pintype "bidirectional"))
    )
    (net (code "87") (name "unconnected-(U2-CTS#-Pad11)") (class "Default")
      (node (ref "U2") (pin "11") (pinfunction "CTS#_11") (pintype "input"))
    )
    (net (code "88") (name "unconnected-(U2-DCD#-Pad10)") (class "Default")
      (node (ref "U2") (pin "10") (pinfunction "DCD#_10") (pintype "input"))
    )
    (net (code "89") (name "unconnected-(U2-DSR#-Pad9)") (class "Default")
      (node (ref "U2") (pin "9") (pinfunction "DSR#_9") (pintype "input"))
    )
    (net (code "90") (name "unconnected-(U2-DTR#-Pad2)") (class "Default")
      (node (ref "U2") (pin "2") (pinfunction "DTR#_2") (pintype "output"))
    )
    (net (code "91") (name "unconnected-(U2-OSCI-Pad27)") (class "Default")
      (node (ref "U2") (pin "27") (pinfunction "OSCI_27") (pintype "input"))
    )
    (net (code "92") (name "unconnected-(U2-OSCO-Pad28)") (class "Default")
      (node (ref "U2") (pin "28") (pinfunction "OSCO_28") (pintype "output"))
    )
    (net (code "93") (name "unconnected-(U2-RI#-Pad6)") (class "Default")
      (node (ref "U2") (pin "6") (pinfunction "RI#_6") (pintype "input"))
    )
    (net (code "94") (name "unconnected-(U2-RTS#-Pad3)") (class "Default")
      (node (ref "U2") (pin "3") (pinfunction "RTS#_3") (pintype "output"))
    )
  )
)
